# SH5_-_RGB_LED.net
KiCad netlist of a schematic drawn in Altium Designer
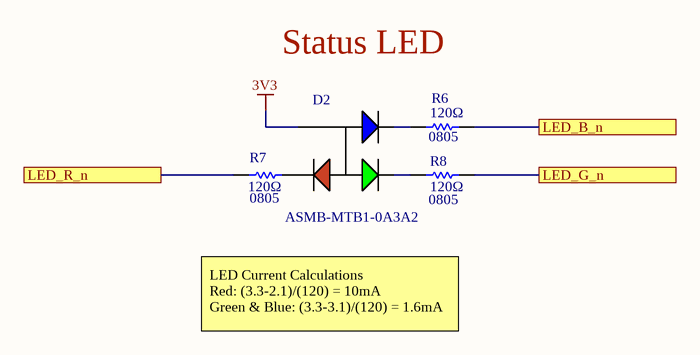
[diagram p0: SH5 - RGB LED.SchDoc]

(export (version "E")
  (design (tool "Eeschema 10.0.6"))
  (components
    (comp (ref "D2")
      (value "LED_RGB")
      (footprint "LED_RGB")
      (description "LED RGB DIFFUSED 4PLCC SMD")
      (fields (field (name "MANUFACTURER PART NUMBER 1") "ASMB-MTB1-0A3A2"))
      (libsource (lib "UWRT_Schematic_Library_2020") (part "LED_RGB"))
    )
    (comp (ref "R6")
      (value "120Ω")
      (footprint "RESC0805")
      (description "RES 120 OHM 1% 1/8W 0805")
      (fields
        (field (name "LCSC PART #") "C17437")
        (field (name "PACKAGE/FOOTPRINT") "0805")
        (field (name "Comment") "RES_120Ω_0805_1%")
      )
      (libsource (lib "UWRT_Schematic_Library_2020") (part "RES_120Ω_0805_1%"))
    )
    (comp (ref "R7")
      (value "120Ω")
      (footprint "RESC0805")
      (description "RES 120 OHM 1% 1/8W 0805")
      (fields
        (field (name "LCSC PART #") "C17437")
        (field (name "PACKAGE/FOOTPRINT") "0805")
        (field (name "Comment") "RES_120Ω_0805_1%")
      )
      (libsource (lib "UWRT_Schematic_Library_2020") (part "RES_120Ω_0805_1%"))
    )
    (comp (ref "R8")
      (value "120Ω")
      (footprint "RESC0805")
      (description "RES 120 OHM 1% 1/8W 0805")
      (fields
        (field (name "LCSC PART #") "C17437")
        (field (name "PACKAGE/FOOTPRINT") "0805")
        (field (name "Comment") "RES_120Ω_0805_1%")
      )
      (libsource (lib "UWRT_Schematic_Library_2020") (part "RES_120Ω_0805_1%"))
    )
  )
  (nets
    (net (code "1") (name "/LED_B_n") (class "Default")
      (node (ref "R6") (pin "2") (pinfunction "2_2") (pintype "passive"))
    )
    (net (code "2") (name "/LED_G_n") (class "Default")
      (node (ref "R8") (pin "2") (pinfunction "2_2") (pintype "passive"))
    )
    (net (code "3") (name "/LED_R_n") (class "Default")
      (node (ref "R7") (pin "1") (pinfunction "1_1") (pintype "passive"))
    )
    (net (code "4") (name "3V3") (class "Default")
      (node (ref "D2") (pin "4") (pinfunction "COMMON_ANODE_4") (pintype "passive"))
    )
    (net (code "5") (name "Net-(D2-CATHODE_(BLUE))") (class "Default")
      (node (ref "D2") (pin "3") (pinfunction "CATHODE_(BLUE)_3") (pintype "passive"))
      (node (ref "R6") (pin "1") (pinfunction "1_1") (pintype "passive"))
    )
    (net (code "6") (name "Net-(D2-CATHODE_(GREEN))") (class "Default")
      (node (ref "D2") (pin "2") (pinfunction "CATHODE_(GREEN)_2") (pintype "passive"))
      (node (ref "R8") (pin "1") (pinfunction "1_1") (pintype "passive"))
    )
    (net (code "7") (name "Net-(D2-CATHODE_(RED))") (class "Default")
      (node (ref "D2") (pin "1") (pinfunction "CATHODE_(RED)_1") (pintype "passive"))
      (node (ref "R7") (pin "2") (pinfunction "2_2") (pintype "passive"))
    )
  )
)
